# Sheet1.net
KiCad netlist of a schematic drawn in Altium Designer
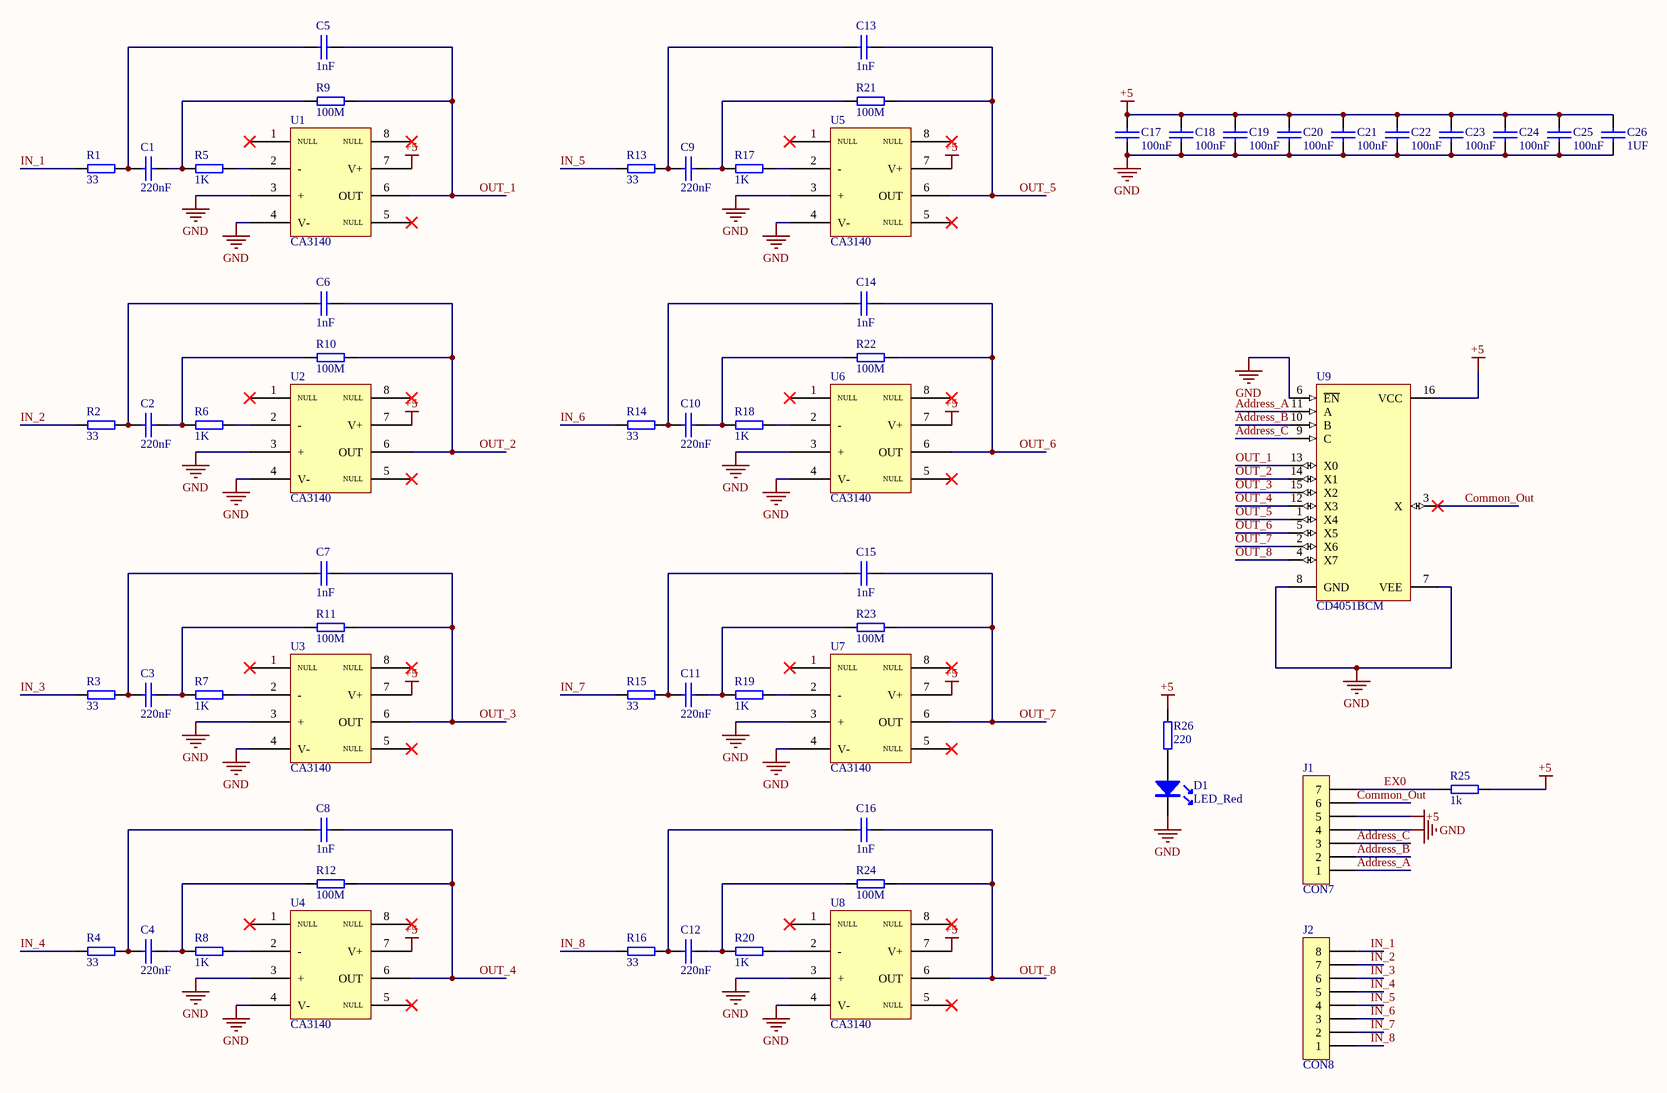
[diagram p0: Sheet1.SchDoc]

(export (version "E")
  (design (tool "Eeschema 10.0.6"))
  (components
    (comp (ref "C1")
      (value "220nF")
      (footprint "6-0805_L")
      (description "电容")
      (libsource (lib "Component") (part "CAP"))
    )
    (comp (ref "C2")
      (value "220nF")
      (footprint "6-0805_L")
      (description "电容")
      (libsource (lib "Component") (part "CAP"))
    )
    (comp (ref "C3")
      (value "220nF")
      (footprint "6-0805_L")
      (description "电容")
      (libsource (lib "Component") (part "CAP"))
    )
    (comp (ref "C4")
      (value "220nF")
      (footprint "6-0805_L")
      (description "电容")
      (libsource (lib "Component") (part "CAP"))
    )
    (comp (ref "C5")
      (value "1nF")
      (footprint "6-0805_L")
      (description "电容")
      (libsource (lib "Component") (part "CAP"))
    )
    (comp (ref "C6")
      (value "1nF")
      (footprint "6-0805_L")
      (description "电容")
      (libsource (lib "Component") (part "CAP"))
    )
    (comp (ref "C7")
      (value "1nF")
      (footprint "6-0805_L")
      (description "电容")
      (libsource (lib "Component") (part "CAP"))
    )
    (comp (ref "C8")
      (value "1nF")
      (footprint "6-0805_L")
      (description "电容")
      (libsource (lib "Component") (part "CAP"))
    )
    (comp (ref "C9")
      (value "220nF")
      (footprint "6-0805_L")
      (description "电容")
      (libsource (lib "Component") (part "CAP"))
    )
    (comp (ref "C10")
      (value "220nF")
      (footprint "6-0805_L")
      (description "电容")
      (libsource (lib "Component") (part "CAP"))
    )
    (comp (ref "C11")
      (value "220nF")
      (footprint "6-0805_L")
      (description "电容")
      (libsource (lib "Component") (part "CAP"))
    )
    (comp (ref "C12")
      (value "220nF")
      (footprint "6-0805_L")
      (description "电容")
      (libsource (lib "Component") (part "CAP"))
    )
    (comp (ref "C13")
      (value "1nF")
      (footprint "6-0805_L")
      (description "电容")
      (libsource (lib "Component") (part "CAP"))
    )
    (comp (ref "C14")
      (value "1nF")
      (footprint "6-0805_L")
      (description "电容")
      (libsource (lib "Component") (part "CAP"))
    )
    (comp (ref "C15")
      (value "1nF")
      (footprint "6-0805_L")
      (description "电容")
      (libsource (lib "Component") (part "CAP"))
    )
    (comp (ref "C16")
      (value "1nF")
      (footprint "6-0805_L")
      (description "电容")
      (libsource (lib "Component") (part "CAP"))
    )
    (comp (ref "C17")
      (value "100nF")
      (footprint "0805C")
      (description "电容")
      (libsource (lib "Component") (part "CAP"))
    )
    (comp (ref "C18")
      (value "100nF")
      (footprint "0805C")
      (description "电容")
      (libsource (lib "Component") (part "CAP"))
    )
    (comp (ref "C19")
      (value "100nF")
      (footprint "0805C")
      (description "电容")
      (libsource (lib "Component") (part "CAP"))
    )
    (comp (ref "C20")
      (value "100nF")
      (footprint "0805C")
      (description "电容")
      (libsource (lib "Component") (part "CAP"))
    )
    (comp (ref "C21")
      (value "100nF")
      (footprint "0805C")
      (description "电容")
      (libsource (lib "Component") (part "CAP"))
    )
    (comp (ref "C22")
      (value "100nF")
      (footprint "0805C")
      (description "电容")
      (libsource (lib "Component") (part "CAP"))
    )
    (comp (ref "C23")
      (value "100nF")
      (footprint "0805C")
      (description "电容")
      (libsource (lib "Component") (part "CAP"))
    )
    (comp (ref "C24")
      (value "100nF")
      (footprint "0805C")
      (description "电容")
      (libsource (lib "Component") (part "CAP"))
    )
    (comp (ref "C25")
      (value "100nF")
      (footprint "0805C")
      (description "电容")
      (libsource (lib "Component") (part "CAP"))
    )
    (comp (ref "C26")
      (value "1UF")
      (footprint "0805C")
      (description "电容")
      (libsource (lib "Component") (part "CAP"))
    )
    (comp (ref "D1")
      (value "LED_Red")
      (footprint "LED0805")
      (description "LED")
      (libsource (lib "Component") (part "LED"))
    )
    (comp (ref "J1")
      (value "CON7")
      (footprint "7P_2.54_VH")
      (description "Connector")
      (libsource (lib "杂元件库") (part "CON7"))
    )
    (comp (ref "J2")
      (value "CON8")
      (footprint "8P_2.54_VH")
      (description "连接器")
      (libsource (lib "Connector") (part "CON8"))
    )
    (comp (ref "R1")
      (value "33")
      (footprint "Miscellaneous Devices:6-0805_M")
      (description "电阻")
      (libsource (lib "Component") (part "RES"))
    )
    (comp (ref "R2")
      (value "33")
      (footprint "Miscellaneous Devices:6-0805_M")
      (description "电阻")
      (libsource (lib "Component") (part "RES"))
    )
    (comp (ref "R3")
      (value "33")
      (footprint "Miscellaneous Devices:6-0805_M")
      (description "电阻")
      (libsource (lib "Component") (part "RES"))
    )
    (comp (ref "R4")
      (value "33")
      (footprint "Miscellaneous Devices:6-0805_M")
      (description "电阻")
      (libsource (lib "Component") (part "RES"))
    )
    (comp (ref "R5")
      (value "1K")
      (footprint "6-0805_M")
      (description "电阻")
      (libsource (lib "Component") (part "RES"))
    )
    (comp (ref "R6")
      (value "1K")
      (footprint "6-0805_M")
      (description "电阻")
      (libsource (lib "Component") (part "RES"))
    )
    (comp (ref "R7")
      (value "1K")
      (footprint "6-0805_M")
      (description "电阻")
      (libsource (lib "Component") (part "RES"))
    )
    (comp (ref "R8")
      (value "1K")
      (footprint "6-0805_M")
      (description "电阻")
      (libsource (lib "Component") (part "RES"))
    )
    (comp (ref "R9")
      (value "100M")
      (footprint "Miscellaneous Devices:6-0805_M")
      (description "电阻")
      (libsource (lib "Component") (part "RES"))
    )
    (comp (ref "R10")
      (value "100M")
      (footprint "Miscellaneous Devices:6-0805_M")
      (description "电阻")
      (libsource (lib "Component") (part "RES"))
    )
    (comp (ref "R11")
      (value "100M")
      (footprint "Miscellaneous Devices:6-0805_M")
      (description "电阻")
      (libsource (lib "Component") (part "RES"))
    )
    (comp (ref "R12")
      (value "100M")
      (footprint "Miscellaneous Devices:6-0805_M")
      (description "电阻")
      (libsource (lib "Component") (part "RES"))
    )
    (comp (ref "R13")
      (value "33")
      (footprint "Miscellaneous Devices:6-0805_M")
      (description "电阻")
      (libsource (lib "Component") (part "RES"))
    )
    (comp (ref "R14")
      (value "33")
      (footprint "Miscellaneous Devices:6-0805_M")
      (description "电阻")
      (libsource (lib "Component") (part "RES"))
    )
    (comp (ref "R15")
      (value "33")
      (footprint "Miscellaneous Devices:6-0805_M")
      (description "电阻")
      (libsource (lib "Component") (part "RES"))
    )
    (comp (ref "R16")
      (value "33")
      (footprint "Miscellaneous Devices:6-0805_M")
      (description "电阻")
      (libsource (lib "Component") (part "RES"))
    )
    (comp (ref "R17")
      (value "1K")
      (footprint "6-0805_M")
      (description "电阻")
      (libsource (lib "Component") (part "RES"))
    )
    (comp (ref "R18")
      (value "1K")
      (footprint "6-0805_M")
      (description "电阻")
      (libsource (lib "Component") (part "RES"))
    )
    (comp (ref "R19")
      (value "1K")
      (footprint "6-0805_M")
      (description "电阻")
      (libsource (lib "Component") (part "RES"))
    )
    (comp (ref "R20")
      (value "1K")
      (footprint "6-0805_M")
      (description "电阻")
      (libsource (lib "Component") (part "RES"))
    )
    (comp (ref "R21")
      (value "100M")
      (footprint "Miscellaneous Devices:6-0805_M")
      (description "电阻")
      (libsource (lib "Component") (part "RES"))
    )
    (comp (ref "R22")
      (value "100M")
      (footprint "Miscellaneous Devices:6-0805_M")
      (description "电阻")
      (libsource (lib "Component") (part "RES"))
    )
    (comp (ref "R23")
      (value "100M")
      (footprint "Miscellaneous Devices:6-0805_M")
      (description "电阻")
      (libsource (lib "Component") (part "RES"))
    )
    (comp (ref "R24")
      (value "100M")
      (footprint "Miscellaneous Devices:6-0805_M")
      (description "电阻")
      (libsource (lib "Component") (part "RES"))
    )
    (comp (ref "R25")
      (value "1k")
      (footprint "6-0805_M")
      (description "电阻")
      (libsource (lib "Component") (part "RES"))
    )
    (comp (ref "R26")
      (value "220")
      (footprint "6-0805_M")
      (description "电阻")
      (libsource (lib "Component") (part "RES"))
    )
    (comp (ref "U1") (value "CA3140") (footprint "SO8_M") (libsource (lib "Mylib") (part "CA3140")))
    (comp (ref "U2") (value "CA3140") (footprint "SO8_M") (libsource (lib "Mylib") (part "CA3140")))
    (comp (ref "U3") (value "CA3140") (footprint "SO8_M") (libsource (lib "Mylib") (part "CA3140")))
    (comp (ref "U4") (value "CA3140") (footprint "SO8_M") (libsource (lib "Mylib") (part "CA3140")))
    (comp (ref "U5") (value "CA3140") (footprint "SO8_M") (libsource (lib "Mylib") (part "CA3140")))
    (comp (ref "U6") (value "CA3140") (footprint "SO8_M") (libsource (lib "Mylib") (part "CA3140")))
    (comp (ref "U7") (value "CA3140") (footprint "SO8_M") (libsource (lib "Mylib") (part "CA3140")))
    (comp (ref "U8") (value "CA3140") (footprint "SO8_M") (libsource (lib "Mylib") (part "CA3140")))
    (comp (ref "U9")
      (value "CD4051BCM")
      (footprint "M16A_N")
      (description "8-Channel Analog Multiplexer/Demultiplexer")
      (fields (field (name "PUBLISHER") "Altium Limited"))
      (libsource (lib "altium-import") (part "root_0_CD4051BCM_"))
    )
  )
  (nets
    (net (code "1") (name "+5") (class "Default")
      (node (ref "C17") (pin "2") (pinfunction "2_2") (pintype "passive"))
      (node (ref "C18") (pin "2") (pinfunction "2_2") (pintype "passive"))
      (node (ref "C19") (pin "2") (pinfunction "2_2") (pintype "passive"))
      (node (ref "C20") (pin "2") (pinfunction "2_2") (pintype "passive"))
      (node (ref "C21") (pin "2") (pinfunction "2_2") (pintype "passive"))
      (node (ref "C22") (pin "2") (pinfunction "2_2") (pintype "passive"))
      (node (ref "C23") (pin "2") (pinfunction "2_2") (pintype "passive"))
      (node (ref "C24") (pin "2") (pinfunction "2_2") (pintype "passive"))
      (node (ref "C25") (pin "2") (pinfunction "2_2") (pintype "passive"))
      (node (ref "C26") (pin "2") (pinfunction "2_2") (pintype "passive"))
      (node (ref "J1") (pin "5") (pinfunction "5_5") (pintype "passive"))
      (node (ref "R25") (pin "2") (pinfunction "2_2") (pintype "passive"))
      (node (ref "R26") (pin "2") (pinfunction "2_2") (pintype "passive"))
      (node (ref "U1") (pin "7") (pinfunction "V+_7") (pintype "passive"))
      (node (ref "U2") (pin "7") (pinfunction "V+_7") (pintype "passive"))
      (node (ref "U3") (pin "7") (pinfunction "V+_7") (pintype "passive"))
      (node (ref "U4") (pin "7") (pinfunction "V+_7") (pintype "passive"))
      (node (ref "U5") (pin "7") (pinfunction "V+_7") (pintype "passive"))
      (node (ref "U6") (pin "7") (pinfunction "V+_7") (pintype "passive"))
      (node (ref "U7") (pin "7") (pinfunction "V+_7") (pintype "passive"))
      (node (ref "U8") (pin "7") (pinfunction "V+_7") (pintype "passive"))
      (node (ref "U9") (pin "16") (pinfunction "VCC_16") (pintype "power_in"))
    )
    (net (code "2") (name "/Address_A") (class "Default")
      (node (ref "J1") (pin "1") (pinfunction "1_1") (pintype "passive"))
      (node (ref "U9") (pin "11") (pinfunction "A_11") (pintype "input"))
    )
    (net (code "3") (name "/Address_B") (class "Default")
      (node (ref "J1") (pin "2") (pinfunction "2_2") (pintype "passive"))
      (node (ref "U9") (pin "10") (pinfunction "B_10") (pintype "input"))
    )
    (net (code "4") (name "/Address_C") (class "Default")
      (node (ref "J1") (pin "3") (pinfunction "3_3") (pintype "passive"))
      (node (ref "U9") (pin "9") (pinfunction "C_9") (pintype "input"))
    )
    (net (code "5") (name "/Common_Out") (class "Default")
      (node (ref "J1") (pin "6") (pinfunction "6_6") (pintype "passive"))
      (node (ref "U9") (pin "3") (pinfunction "X_3") (pintype "bidirectional"))
    )
    (net (code "6") (name "/EX0") (class "Default")
      (node (ref "J1") (pin "7") (pinfunction "7_7") (pintype "passive"))
      (node (ref "R25") (pin "1") (pinfunction "1_1") (pintype "passive"))
    )
    (net (code "7") (name "/IN_1") (class "Default")
      (node (ref "J2") (pin "8") (pinfunction "8_8") (pintype "passive"))
      (node (ref "R1") (pin "1") (pinfunction "1_1") (pintype "passive"))
    )
    (net (code "8") (name "/IN_2") (class "Default")
      (node (ref "J2") (pin "7") (pinfunction "7_7") (pintype "passive"))
      (node (ref "R2") (pin "1") (pinfunction "1_1") (pintype "passive"))
    )
    (net (code "9") (name "/IN_3") (class "Default")
      (node (ref "J2") (pin "6") (pinfunction "6_6") (pintype "passive"))
      (node (ref "R3") (pin "1") (pinfunction "1_1") (pintype "passive"))
    )
    (net (code "10") (name "/IN_4") (class "Default")
      (node (ref "J2") (pin "5") (pinfunction "5_5") (pintype "passive"))
      (node (ref "R4") (pin "1") (pinfunction "1_1") (pintype "passive"))
    )
    (net (code "11") (name "/IN_5") (class "Default")
      (node (ref "J2") (pin "4") (pinfunction "4_4") (pintype "passive"))
      (node (ref "R13") (pin "1") (pinfunction "1_1") (pintype "passive"))
    )
    (net (code "12") (name "/IN_6") (class "Default")
      (node (ref "J2") (pin "3") (pinfunction "3_3") (pintype "passive"))
      (node (ref "R14") (pin "1") (pinfunction "1_1") (pintype "passive"))
    )
    (net (code "13") (name "/IN_7") (class "Default")
      (node (ref "J2") (pin "2") (pinfunction "2_2") (pintype "passive"))
      (node (ref "R15") (pin "1") (pinfunction "1_1") (pintype "passive"))
    )
    (net (code "14") (name "/IN_8") (class "Default")
      (node (ref "J2") (pin "1") (pinfunction "1_1") (pintype "passive"))
      (node (ref "R16") (pin "1") (pinfunction "1_1") (pintype "passive"))
    )
    (net (code "15") (name "/OUT_1") (class "Default")
      (node (ref "C5") (pin "2") (pinfunction "2_2") (pintype "passive"))
      (node (ref "R9") (pin "2") (pinfunction "2_2") (pintype "passive"))
      (node (ref "U1") (pin "6") (pinfunction "OUT_6") (pintype "passive"))
      (node (ref "U9") (pin "13") (pinfunction "X0_13") (pintype "bidirectional"))
    )
    (net (code "16") (name "/OUT_2") (class "Default")
      (node (ref "C6") (pin "2") (pinfunction "2_2") (pintype "passive"))
      (node (ref "R10") (pin "2") (pinfunction "2_2") (pintype "passive"))
      (node (ref "U2") (pin "6") (pinfunction "OUT_6") (pintype "passive"))
      (node (ref "U9") (pin "14") (pinfunction "X1_14") (pintype "bidirectional"))
    )
    (net (code "17") (name "/OUT_3") (class "Default")
      (node (ref "C7") (pin "2") (pinfunction "2_2") (pintype "passive"))
      (node (ref "R11") (pin "2") (pinfunction "2_2") (pintype "passive"))
      (node (ref "U3") (pin "6") (pinfunction "OUT_6") (pintype "passive"))
      (node (ref "U9") (pin "15") (pinfunction "X2_15") (pintype "bidirectional"))
    )
    (net (code "18") (name "/OUT_4") (class "Default")
      (node (ref "C8") (pin "2") (pinfunction "2_2") (pintype "passive"))
      (node (ref "R12") (pin "2") (pinfunction "2_2") (pintype "passive"))
      (node (ref "U4") (pin "6") (pinfunction "OUT_6") (pintype "passive"))
      (node (ref "U9") (pin "12") (pinfunction "X3_12") (pintype "bidirectional"))
    )
    (net (code "19") (name "/OUT_5") (class "Default")
      (node (ref "C13") (pin "2") (pinfunction "2_2") (pintype "passive"))
      (node (ref "R21") (pin "2") (pinfunction "2_2") (pintype "passive"))
      (node (ref "U5") (pin "6") (pinfunction "OUT_6") (pintype "passive"))
      (node (ref "U9") (pin "1") (pinfunction "X4_1") (pintype "bidirectional"))
    )
    (net (code "20") (name "/OUT_6") (class "Default")
      (node (ref "C14") (pin "2") (pinfunction "2_2") (pintype "passive"))
      (node (ref "R22") (pin "2") (pinfunction "2_2") (pintype "passive"))
      (node (ref "U6") (pin "6") (pinfunction "OUT_6") (pintype "passive"))
      (node (ref "U9") (pin "5") (pinfunction "X5_5") (pintype "bidirectional"))
    )
    (net (code "21") (name "/OUT_7") (class "Default")
      (node (ref "C15") (pin "2") (pinfunction "2_2") (pintype "passive"))
      (node (ref "R23") (pin "2") (pinfunction "2_2") (pintype "passive"))
      (node (ref "U7") (pin "6") (pinfunction "OUT_6") (pintype "passive"))
      (node (ref "U9") (pin "2") (pinfunction "X6_2") (pintype "bidirectional"))
    )
    (net (code "22") (name "/OUT_8") (class "Default")
      (node (ref "C16") (pin "2") (pinfunction "2_2") (pintype "passive"))
      (node (ref "R24") (pin "2") (pinfunction "2_2") (pintype "passive"))
      (node (ref "U8") (pin "6") (pinfunction "OUT_6") (pintype "passive"))
      (node (ref "U9") (pin "4") (pinfunction "X7_4") (pintype "bidirectional"))
    )
    (net (code "23") (name "GND") (class "Default")
      (node (ref "C17") (pin "1") (pinfunction "1_1") (pintype "passive"))
      (node (ref "C18") (pin "1") (pinfunction "1_1") (pintype "passive"))
      (node (ref "C19") (pin "1") (pinfunction "1_1") (pintype "passive"))
      (node (ref "C20") (pin "1") (pinfunction "1_1") (pintype "passive"))
      (node (ref "C21") (pin "1") (pinfunction "1_1") (pintype "passive"))
      (node (ref "C22") (pin "1") (pinfunction "1_1") (pintype "passive"))
      (node (ref "C23") (pin "1") (pinfunction "1_1") (pintype "passive"))
      (node (ref "C24") (pin "1") (pinfunction "1_1") (pintype "passive"))
      (node (ref "C25") (pin "1") (pinfunction "1_1") (pintype "passive"))
      (node (ref "C26") (pin "1") (pinfunction "1_1") (pintype "passive"))
      (node (ref "D1") (pin "2") (pinfunction "2_2") (pintype "passive"))
      (node (ref "J1") (pin "4") (pinfunction "4_4") (pintype "passive"))
      (node (ref "U1") (pin "3") (pinfunction "+_3") (pintype "passive"))
      (node (ref "U1") (pin "4") (pinfunction "V-_4") (pintype "passive"))
      (node (ref "U2") (pin "3") (pinfunction "+_3") (pintype "passive"))
      (node (ref "U2") (pin "4") (pinfunction "V-_4") (pintype "passive"))
      (node (ref "U3") (pin "3") (pinfunction "+_3") (pintype "passive"))
      (node (ref "U3") (pin "4") (pinfunction "V-_4") (pintype "passive"))
      (node (ref "U4") (pin "3") (pinfunction "+_3") (pintype "passive"))
      (node (ref "U4") (pin "4") (pinfunction "V-_4") (pintype "passive"))
      (node (ref "U5") (pin "3") (pinfunction "+_3") (pintype "passive"))
      (node (ref "U5") (pin "4") (pinfunction "V-_4") (pintype "passive"))
      (node (ref "U6") (pin "3") (pinfunction "+_3") (pintype "passive"))
      (node (ref "U6") (pin "4") (pinfunction "V-_4") (pintype "passive"))
      (node (ref "U7") (pin "3") (pinfunction "+_3") (pintype "passive"))
      (node (ref "U7") (pin "4") (pinfunction "V-_4") (pintype "passive"))
      (node (ref "U8") (pin "3") (pinfunction "+_3") (pintype "passive"))
      (node (ref "U8") (pin "4") (pinfunction "V-_4") (pintype "passive"))
      (node (ref "U9") (pin "6") (pinfunction "~{EN}_6") (pintype "input"))
      (node (ref "U9") (pin "7") (pinfunction "VEE_7") (pintype "power_in"))
      (node (ref "U9") (pin "8") (pinfunction "GND_8") (pintype "power_in"))
    )
    (net (code "24") (name "Net-(C1-Pad1)") (class "Default")
      (node (ref "C1") (pin "1") (pinfunction "1_1") (pintype "passive"))
      (node (ref "C5") (pin "1") (pinfunction "1_1") (pintype "passive"))
      (node (ref "R1") (pin "2") (pinfunction "2_2") (pintype "passive"))
    )
    (net (code "25") (name "Net-(C1-Pad2)") (class "Default")
      (node (ref "C1") (pin "2") (pinfunction "2_2") (pintype "passive"))
      (node (ref "R5") (pin "1") (pinfunction "1_1") (pintype "passive"))
      (node (ref "R9") (pin "1") (pinfunction "1_1") (pintype "passive"))
    )
    (net (code "26") (name "Net-(C2-Pad1)") (class "Default")
      (node (ref "C2") (pin "1") (pinfunction "1_1") (pintype "passive"))
      (node (ref "C6") (pin "1") (pinfunction "1_1") (pintype "passive"))
      (node (ref "R2") (pin "2") (pinfunction "2_2") (pintype "passive"))
    )
    (net (code "27") (name "Net-(C2-Pad2)") (class "Default")
      (node (ref "C2") (pin "2") (pinfunction "2_2") (pintype "passive"))
      (node (ref "R10") (pin "1") (pinfunction "1_1") (pintype "passive"))
      (node (ref "R6") (pin "1") (pinfunction "1_1") (pintype "passive"))
    )
    (net (code "28") (name "Net-(C3-Pad1)") (class "Default")
      (node (ref "C3") (pin "1") (pinfunction "1_1") (pintype "passive"))
      (node (ref "C7") (pin "1") (pinfunction "1_1") (pintype "passive"))
      (node (ref "R3") (pin "2") (pinfunction "2_2") (pintype "passive"))
    )
    (net (code "29") (name "Net-(C3-Pad2)") (class "Default")
      (node (ref "C3") (pin "2") (pinfunction "2_2") (pintype "passive"))
      (node (ref "R11") (pin "1") (pinfunction "1_1") (pintype "passive"))
      (node (ref "R7") (pin "1") (pinfunction "1_1") (pintype "passive"))
    )
    (net (code "30") (name "Net-(C4-Pad1)") (class "Default")
      (node (ref "C4") (pin "1") (pinfunction "1_1") (pintype "passive"))
      (node (ref "C8") (pin "1") (pinfunction "1_1") (pintype "passive"))
      (node (ref "R4") (pin "2") (pinfunction "2_2") (pintype "passive"))
    )
    (net (code "31") (name "Net-(C4-Pad2)") (class "Default")
      (node (ref "C4") (pin "2") (pinfunction "2_2") (pintype "passive"))
      (node (ref "R12") (pin "1") (pinfunction "1_1") (pintype "passive"))
      (node (ref "R8") (pin "1") (pinfunction "1_1") (pintype "passive"))
    )
    (net (code "32") (name "Net-(C9-Pad2)") (class "Default")
      (node (ref "C9") (pin "2") (pinfunction "2_2") (pintype "passive"))
      (node (ref "R17") (pin "1") (pinfunction "1_1") (pintype "passive"))
      (node (ref "R21") (pin "1") (pinfunction "1_1") (pintype "passive"))
    )
    (net (code "33") (name "Net-(C10-Pad1)") (class "Default")
      (node (ref "C10") (pin "1") (pinfunction "1_1") (pintype "passive"))
      (node (ref "C14") (pin "1") (pinfunction "1_1") (pintype "passive"))
      (node (ref "R14") (pin "2") (pinfunction "2_2") (pintype "passive"))
    )
    (net (code "34") (name "Net-(C10-Pad2)") (class "Default")
      (node (ref "C10") (pin "2") (pinfunction "2_2") (pintype "passive"))
      (node (ref "R18") (pin "1") (pinfunction "1_1") (pintype "passive"))
      (node (ref "R22") (pin "1") (pinfunction "1_1") (pintype "passive"))
    )
    (net (code "35") (name "Net-(C11-Pad1)") (class "Default")
      (node (ref "C11") (pin "1") (pinfunction "1_1") (pintype "passive"))
      (node (ref "C15") (pin "1") (pinfunction "1_1") (pintype "passive"))
      (node (ref "R15") (pin "2") (pinfunction "2_2") (pintype "passive"))
    )
    (net (code "36") (name "Net-(C11-Pad2)") (class "Default")
      (node (ref "C11") (pin "2") (pinfunction "2_2") (pintype "passive"))
      (node (ref "R19") (pin "1") (pinfunction "1_1") (pintype "passive"))
      (node (ref "R23") (pin "1") (pinfunction "1_1") (pintype "passive"))
    )
    (net (code "37") (name "Net-(C12-Pad1)") (class "Default")
      (node (ref "C12") (pin "1") (pinfunction "1_1") (pintype "passive"))
      (node (ref "C16") (pin "1") (pinfunction "1_1") (pintype "passive"))
      (node (ref "R16") (pin "2") (pinfunction "2_2") (pintype "passive"))
    )
    (net (code "38") (name "Net-(C12-Pad2)") (class "Default")
      (node (ref "C12") (pin "2") (pinfunction "2_2") (pintype "passive"))
      (node (ref "R20") (pin "1") (pinfunction "1_1") (pintype "passive"))
      (node (ref "R24") (pin "1") (pinfunction "1_1") (pintype "passive"))
    )
    (net (code "39") (name "Net-(C13-Pad1)") (class "Default")
      (node (ref "C13") (pin "1") (pinfunction "1_1") (pintype "passive"))
      (node (ref "C9") (pin "1") (pinfunction "1_1") (pintype "passive"))
      (node (ref "R13") (pin "2") (pinfunction "2_2") (pintype "passive"))
    )
    (net (code "40") (name "Net-(D1-Pad1)") (class "Default")
      (node (ref "D1") (pin "1") (pinfunction "1_1") (pintype "passive"))
      (node (ref "R26") (pin "1") (pinfunction "1_1") (pintype "passive"))
    )
    (net (code "41") (name "Net-(U1--)") (class "Default")
      (node (ref "R5") (pin "2") (pinfunction "2_2") (pintype "passive"))
      (node (ref "U1") (pin "2") (pinfunction "-_2") (pintype "passive"))
    )
    (net (code "42") (name "Net-(U2--)") (class "Default")
      (node (ref "R6") (pin "2") (pinfunction "2_2") (pintype "passive"))
      (node (ref "U2") (pin "2") (pinfunction "-_2") (pintype "passive"))
    )
    (net (code "43") (name "Net-(U3--)") (class "Default")
      (node (ref "R7") (pin "2") (pinfunction "2_2") (pintype "passive"))
      (node (ref "U3") (pin "2") (pinfunction "-_2") (pintype "passive"))
    )
    (net (code "44") (name "Net-(U4--)") (class "Default")
      (node (ref "R8") (pin "2") (pinfunction "2_2") (pintype "passive"))
      (node (ref "U4") (pin "2") (pinfunction "-_2") (pintype "passive"))
    )
    (net (code "45") (name "Net-(U5--)") (class "Default")
      (node (ref "R17") (pin "2") (pinfunction "2_2") (pintype "passive"))
      (node (ref "U5") (pin "2") (pinfunction "-_2") (pintype "passive"))
    )
    (net (code "46") (name "Net-(U6--)") (class "Default")
      (node (ref "R18") (pin "2") (pinfunction "2_2") (pintype "passive"))
      (node (ref "U6") (pin "2") (pinfunction "-_2") (pintype "passive"))
    )
    (net (code "47") (name "Net-(U7--)") (class "Default")
      (node (ref "R19") (pin "2") (pinfunction "2_2") (pintype "passive"))
      (node (ref "U7") (pin "2") (pinfunction "-_2") (pintype "passive"))
    )
    (net (code "48") (name "Net-(U8--)") (class "Default")
      (node (ref "R20") (pin "2") (pinfunction "2_2") (pintype "passive"))
      (node (ref "U8") (pin "2") (pinfunction "-_2") (pintype "passive"))
    )
    (net (code "49") (name "unconnected-(U1-NULL-Pad1)") (class "Default")
      (node (ref "U1") (pin "1") (pinfunction "NULL_1") (pintype "passive+no_connect"))
    )
    (net (code "50") (name "unconnected-(U1-NULL-Pad5)") (class "Default")
      (node (ref "U1") (pin "5") (pinfunction "NULL_5") (pintype "passive+no_connect"))
    )
    (net (code "51") (name "unconnected-(U1-NULL-Pad8)") (class "Default")
      (node (ref "U1") (pin "8") (pinfunction "NULL_8") (pintype "passive+no_connect"))
    )
    (net (code "52") (name "unconnected-(U2-NULL-Pad1)") (class "Default")
      (node (ref "U2") (pin "1") (pinfunction "NULL_1") (pintype "passive+no_connect"))
    )
    (net (code "53") (name "unconnected-(U2-NULL-Pad5)") (class "Default")
      (node (ref "U2") (pin "5") (pinfunction "NULL_5") (pintype "passive+no_connect"))
    )
    (net (code "54") (name "unconnected-(U2-NULL-Pad8)") (class "Default")
      (node (ref "U2") (pin "8") (pinfunction "NULL_8") (pintype "passive+no_connect"))
    )
    (net (code "55") (name "unconnected-(U3-NULL-Pad1)") (class "Default")
      (node (ref "U3") (pin "1") (pinfunction "NULL_1") (pintype "passive+no_connect"))
    )
    (net (code "56") (name "unconnected-(U3-NULL-Pad5)") (class "Default")
      (node (ref "U3") (pin "5") (pinfunction "NULL_5") (pintype "passive+no_connect"))
    )
    (net (code "57") (name "unconnected-(U3-NULL-Pad8)") (class "Default")
      (node (ref "U3") (pin "8") (pinfunction "NULL_8") (pintype "passive+no_connect"))
    )
    (net (code "58") (name "unconnected-(U4-NULL-Pad1)") (class "Default")
      (node (ref "U4") (pin "1") (pinfunction "NULL_1") (pintype "passive+no_connect"))
    )
    (net (code "59") (name "unconnected-(U4-NULL-Pad5)") (class "Default")
      (node (ref "U4") (pin "5") (pinfunction "NULL_5") (pintype "passive+no_connect"))
    )
    (net (code "60") (name "unconnected-(U4-NULL-Pad8)") (class "Default")
      (node (ref "U4") (pin "8") (pinfunction "NULL_8") (pintype "passive+no_connect"))
    )
    (net (code "61") (name "unconnected-(U5-NULL-Pad1)") (class "Default")
      (node (ref "U5") (pin "1") (pinfunction "NULL_1") (pintype "passive+no_connect"))
    )
    (net (code "62") (name "unconnected-(U5-NULL-Pad5)") (class "Default")
      (node (ref "U5") (pin "5") (pinfunction "NULL_5") (pintype "passive+no_connect"))
    )
    (net (code "63") (name "unconnected-(U5-NULL-Pad8)") (class "Default")
      (node (ref "U5") (pin "8") (pinfunction "NULL_8") (pintype "passive+no_connect"))
    )
    (net (code "64") (name "unconnected-(U6-NULL-Pad1)") (class "Default")
      (node (ref "U6") (pin "1") (pinfunction "NULL_1") (pintype "passive+no_connect"))
    )
    (net (code "65") (name "unconnected-(U6-NULL-Pad5)") (class "Default")
      (node (ref "U6") (pin "5") (pinfunction "NULL_5") (pintype "passive+no_connect"))
    )
    (net (code "66") (name "unconnected-(U6-NULL-Pad8)") (class "Default")
      (node (ref "U6") (pin "8") (pinfunction "NULL_8") (pintype "passive+no_connect"))
    )
    (net (code "67") (name "unconnected-(U7-NULL-Pad1)") (class "Default")
      (node (ref "U7") (pin "1") (pinfunction "NULL_1") (pintype "passive+no_connect"))
    )
    (net (code "68") (name "unconnected-(U7-NULL-Pad5)") (class "Default")
      (node (ref "U7") (pin "5") (pinfunction "NULL_5") (pintype "passive+no_connect"))
    )
    (net (code "69") (name "unconnected-(U7-NULL-Pad8)") (class "Default")
      (node (ref "U7") (pin "8") (pinfunction "NULL_8") (pintype "passive+no_connect"))
    )
    (net (code "70") (name "unconnected-(U8-NULL-Pad1)") (class "Default")
      (node (ref "U8") (pin "1") (pinfunction "NULL_1") (pintype "passive+no_connect"))
    )
    (net (code "71") (name "unconnected-(U8-NULL-Pad5)") (class "Default")
      (node (ref "U8") (pin "5") (pinfunction "NULL_5") (pintype "passive+no_connect"))
    )
    (net (code "72") (name "unconnected-(U8-NULL-Pad8)") (class "Default")
      (node (ref "U8") (pin "8") (pinfunction "NULL_8") (pintype "passive+no_connect"))
    )
  )
)
